# UI.net
KiCad netlist of a schematic drawn in Altium Designer
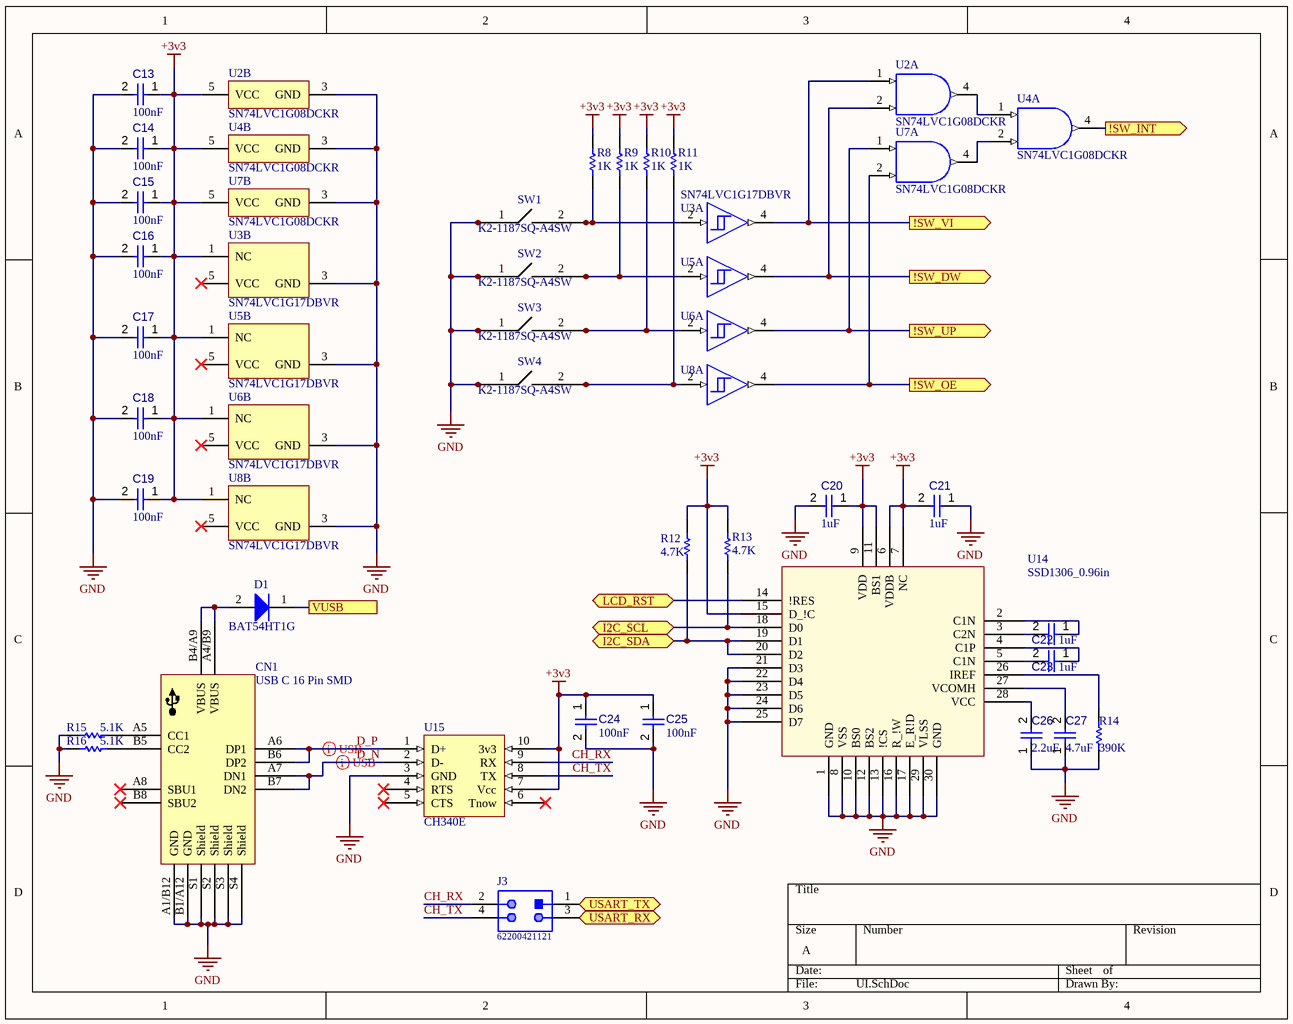
[diagram p0: UI.SchDoc]

(export (version "E")
  (design (tool "Eeschema 10.0.6"))
  (components
    (comp (ref "C13")
      (value "100nF")
      (footprint "CAPC2013X95X50ML10T25")
      (description "Chip Capacitor, 100 nF, +/- 10%, 50 V, 0805 (2012 Metric)")
      (fields (field (name "TOLERANCE") "10%") (field (name "Comment") "Capacitor 100 nF +/-10% 50 V 0805"))
      (libsource (lib "Aditya Sehgal") (part "CAP-NP-2"))
    )
    (comp (ref "C14")
      (value "100nF")
      (footprint "CAPC2013X95X50ML10T25")
      (description "Chip Capacitor, 100 nF, +/- 10%, 50 V, 0805 (2012 Metric)")
      (fields (field (name "TOLERANCE") "10%") (field (name "Comment") "Capacitor 100 nF +/-10% 50 V 0805"))
      (libsource (lib "Aditya Sehgal") (part "CAP-NP-2"))
    )
    (comp (ref "C15")
      (value "100nF")
      (footprint "CAPC2013X95X50ML10T25")
      (description "Chip Capacitor, 100 nF, +/- 10%, 50 V, 0805 (2012 Metric)")
      (fields (field (name "TOLERANCE") "10%") (field (name "Comment") "Capacitor 100 nF +/-10% 50 V 0805"))
      (libsource (lib "Aditya Sehgal") (part "CAP-NP-2"))
    )
    (comp (ref "C16")
      (value "100nF")
      (footprint "CAPC2013X95X50ML10T25")
      (description "Chip Capacitor, 100 nF, +/- 10%, 50 V, 0805 (2012 Metric)")
      (fields (field (name "TOLERANCE") "10%") (field (name "Comment") "Capacitor 100 nF +/-10% 50 V 0805"))
      (libsource (lib "Aditya Sehgal") (part "CAP-NP-2"))
    )
    (comp (ref "C17")
      (value "100nF")
      (footprint "CAPC2013X95X50ML10T25")
      (description "Chip Capacitor, 100 nF, +/- 10%, 50 V, 0805 (2012 Metric)")
      (fields (field (name "TOLERANCE") "10%") (field (name "Comment") "Capacitor 100 nF +/-10% 50 V 0805"))
      (libsource (lib "Aditya Sehgal") (part "CAP-NP-2"))
    )
    (comp (ref "C18")
      (value "100nF")
      (footprint "CAPC2013X95X50ML10T25")
      (description "Chip Capacitor, 100 nF, +/- 10%, 50 V, 0805 (2012 Metric)")
      (fields (field (name "TOLERANCE") "10%") (field (name "Comment") "Capacitor 100 nF +/-10% 50 V 0805"))
      (libsource (lib "Aditya Sehgal") (part "CAP-NP-2"))
    )
    (comp (ref "C19")
      (value "100nF")
      (footprint "CAPC2013X95X50ML10T25")
      (description "Chip Capacitor, 100 nF, +/- 10%, 50 V, 0805 (2012 Metric)")
      (fields (field (name "TOLERANCE") "10%") (field (name "Comment") "Capacitor 100 nF +/-10% 50 V 0805"))
      (libsource (lib "Aditya Sehgal") (part "CAP-NP-2"))
    )
    (comp (ref "C20")
      (value "1uF")
      (footprint "CAPC2013X95X50ML10T25")
      (description "Chip Capacitor, 100 nF, +/- 10%, 50 V, 0805 (2012 Metric)")
      (fields (field (name "TOLERANCE") "10%") (field (name "Comment") "Capacitor 100 nF +/-10% 50 V 0805"))
      (libsource (lib "Aditya Sehgal") (part "CAP-NP-2"))
    )
    (comp (ref "C21")
      (value "1uF")
      (footprint "CAPC2013X95X50ML10T25")
      (description "Chip Capacitor, 100 nF, +/- 10%, 50 V, 0805 (2012 Metric)")
      (fields (field (name "TOLERANCE") "10%") (field (name "Comment") "Capacitor 100 nF +/-10% 50 V 0805"))
      (libsource (lib "Aditya Sehgal") (part "CAP-NP-2"))
    )
    (comp (ref "C22")
      (value "1uF")
      (footprint "CAPC2013X95X50ML10T25")
      (description "Chip Capacitor, 100 nF, +/- 10%, 50 V, 0805 (2012 Metric)")
      (fields (field (name "TOLERANCE") "10%") (field (name "Comment") "Capacitor 100 nF +/-10% 50 V 0805"))
      (libsource (lib "Aditya Sehgal") (part "CAP-NP-2"))
    )
    (comp (ref "C23")
      (value "1uF")
      (footprint "CAPC2013X95X50ML10T25")
      (description "Chip Capacitor, 100 nF, +/- 10%, 50 V, 0805 (2012 Metric)")
      (fields (field (name "TOLERANCE") "10%") (field (name "Comment") "Capacitor 100 nF +/-10% 50 V 0805"))
      (libsource (lib "Aditya Sehgal") (part "CAP-NP-2"))
    )
    (comp (ref "C24")
      (value "100nF")
      (footprint "CAPC2013X95X50ML10T25")
      (description "Chip Capacitor, 100 nF, +/- 10%, 50 V, 0805 (2012 Metric)")
      (fields (field (name "TOLERANCE") "10%") (field (name "Comment") "Capacitor 100 nF +/-10% 50 V 0805"))
      (libsource (lib "Aditya Sehgal") (part "CAP-NP-2"))
    )
    (comp (ref "C25")
      (value "100nF")
      (footprint "CAPC2013X95X50ML10T25")
      (description "Chip Capacitor, 100 nF, +/- 10%, 50 V, 0805 (2012 Metric)")
      (fields (field (name "TOLERANCE") "10%") (field (name "Comment") "Capacitor 100 nF +/-10% 50 V 0805"))
      (libsource (lib "Aditya Sehgal") (part "CAP-NP-2"))
    )
    (comp (ref "C26")
      (value "2.2uF")
      (footprint "CAPC2013X95X50ML10T25")
      (description "Chip Capacitor, 100 nF, +/- 10%, 50 V, 0805 (2012 Metric)")
      (fields (field (name "TOLERANCE") "10%") (field (name "Comment") "Capacitor 100 nF +/-10% 50 V 0805"))
      (libsource (lib "Aditya Sehgal") (part "CAP-NP-2"))
    )
    (comp (ref "C27")
      (value "4.7uF")
      (footprint "CAPC2013X95X50ML10T25")
      (description "Chip Capacitor, 100 nF, +/- 10%, 50 V, 0805 (2012 Metric)")
      (fields (field (name "TOLERANCE") "10%") (field (name "Comment") "Capacitor 100 nF +/-10% 50 V 0805"))
      (libsource (lib "Aditya Sehgal") (part "CAP-NP-2"))
    )
    (comp (ref "CN1")
      (value "USB C 16 Pin SMD")
      (footprint "USB C 16 Pin SMD-Footprint-1")
      (description "C167321 Jing Extension")
      (libsource (lib "Aditya Sehgal") (part "USB C 16 Pin SMD"))
    )
    (comp (ref "D1")
      (value "BAT54HT1G")
      (footprint "ONSC-SOD-323-2-477-02_V")
      (description "Schottky Barrier Diode, 2-Pin SOD-323, Pb-Free, Tape and Reel")
      (fields (field (name "MANUFACTURER") "On Semiconductor"))
      (libsource (lib "Altium Content Vault") (part "ONSC-D-K1A2-2"))
    )
    (comp (ref "J3")
      (value "62200421121")
      (footprint "62200421121")
      (description "THT Vertical Pin Header WR-PHD, Pitch 1.27 mm, Dual Row, 4 pins")
      (fields (field (name "MANUFACTURER") "Wurth Elektronik") (field (name "PUBLISHER") "WurthElektronik"))
      (libsource (lib "Altium Content Vault") (part "WE-CN-2P-M-R4"))
    )
    (comp (ref "R8")
      (value "1K")
      (footprint "RESC2013X50X35ML15T15")
      (description "Chip Resistor, 0 Ohm, +/- 1%, 125 mW, -55 to 155 degC, 0805 (2012 Metric)")
      (fields (field (name "TOLERANCE") "1%") (field (name "POWER") "125mW"))
      (libsource (lib "Aditya Sehgal") (part "RES-2"))
    )
    (comp (ref "R9")
      (value "1K")
      (footprint "RESC2013X50X35ML15T15")
      (description "Chip Resistor, 0 Ohm, +/- 1%, 125 mW, -55 to 155 degC, 0805 (2012 Metric)")
      (fields (field (name "TOLERANCE") "1%") (field (name "POWER") "125mW"))
      (libsource (lib "Aditya Sehgal") (part "RES-2"))
    )
    (comp (ref "R10")
      (value "1K")
      (footprint "RESC2013X50X35ML15T15")
      (description "Chip Resistor, 0 Ohm, +/- 1%, 125 mW, -55 to 155 degC, 0805 (2012 Metric)")
      (fields (field (name "TOLERANCE") "1%") (field (name "POWER") "125mW"))
      (libsource (lib "Aditya Sehgal") (part "RES-2"))
    )
    (comp (ref "R11")
      (value "1K")
      (footprint "RESC2013X50X35ML15T15")
      (description "Chip Resistor, 0 Ohm, +/- 1%, 125 mW, -55 to 155 degC, 0805 (2012 Metric)")
      (fields (field (name "TOLERANCE") "1%") (field (name "POWER") "125mW"))
      (libsource (lib "Aditya Sehgal") (part "RES-2"))
    )
    (comp (ref "R12")
      (value "4.7K")
      (footprint "RESC2013X50X35ML15T15")
      (description "Chip Resistor, 0 Ohm, +/- 1%, 125 mW, -55 to 155 degC, 0805 (2012 Metric)")
      (fields (field (name "TOLERANCE") "1%") (field (name "POWER") "125mW"))
      (libsource (lib "Aditya Sehgal") (part "RES-2"))
    )
    (comp (ref "R13")
      (value "4.7K")
      (footprint "RESC2013X50X35ML15T15")
      (description "Chip Resistor, 0 Ohm, +/- 1%, 125 mW, -55 to 155 degC, 0805 (2012 Metric)")
      (fields (field (name "TOLERANCE") "1%") (field (name "POWER") "125mW"))
      (libsource (lib "Aditya Sehgal") (part "RES-2"))
    )
    (comp (ref "R14")
      (value "390K")
      (footprint "RESC2013X50X35ML15T15")
      (description "Chip Resistor, 0 Ohm, +/- 1%, 125 mW, -55 to 155 degC, 0805 (2012 Metric)")
      (fields (field (name "TOLERANCE") "1%") (field (name "POWER") "125mW"))
      (libsource (lib "Aditya Sehgal") (part "RES-2"))
    )
    (comp (ref "R15")
      (value "5.1K")
      (footprint "RESC2013X50X35ML15T15")
      (description "Chip Resistor, 0 Ohm, +/- 1%, 125 mW, -55 to 155 degC, 0805 (2012 Metric)")
      (fields (field (name "TOLERANCE") "1%") (field (name "POWER") "125mW"))
      (libsource (lib "Aditya Sehgal") (part "RES-2"))
    )
    (comp (ref "R16")
      (value "5.1K")
      (footprint "RESC2013X50X35ML15T15")
      (description "Chip Resistor, 0 Ohm, +/- 1%, 125 mW, -55 to 155 degC, 0805 (2012 Metric)")
      (fields (field (name "TOLERANCE") "1%") (field (name "POWER") "125mW"))
      (libsource (lib "Aditya Sehgal") (part "RES-2"))
    )
    (comp (ref "SW1")
      (value "K2-1187SQ-A4SW")
      (footprint "K2-1187SQ-A4SW-Footprint-1")
      (description "4 pin SMD switch")
      (libsource (lib "Aditya Sehgal") (part "K2-1187SQ-A4SW"))
    )
    (comp (ref "SW2")
      (value "K2-1187SQ-A4SW")
      (footprint "K2-1187SQ-A4SW-Footprint-1")
      (description "4 pin SMD switch")
      (libsource (lib "Aditya Sehgal") (part "K2-1187SQ-A4SW"))
    )
    (comp (ref "SW3")
      (value "K2-1187SQ-A4SW")
      (footprint "K2-1187SQ-A4SW-Footprint-1")
      (description "4 pin SMD switch")
      (libsource (lib "Aditya Sehgal") (part "K2-1187SQ-A4SW"))
    )
    (comp (ref "SW4")
      (value "K2-1187SQ-A4SW")
      (footprint "K2-1187SQ-A4SW-Footprint-1")
      (description "4 pin SMD switch")
      (libsource (lib "Aditya Sehgal") (part "K2-1187SQ-A4SW"))
    )
    (comp (ref "U2")
      (value "SN74LVC1G08DCKR")
      (footprint "DCK0005A_M")
      (description "Single 2-Input Positive-AND Gate, DCK0005A, LARGE T&R")
      (fields
        (field (name "GENERIC PART NUMBER") "SN74LVC1G08")
        (field (name "MANUFACTURER") "Texas Instruments")
      )
      (libsource (lib "Altium Content Vault") (part "TI-SN74XXX1X08-5"))
    )
    (comp (ref "U3")
      (value "SN74LVC1G17DBVR")
      (footprint "DBV0005A_L")
      (description "Single Schmitt-Trigger Buffer, DBV0005A, LARGE T&R")
      (fields
        (field (name "MANUFACTURER") "Texas Instruments")
        (field (name "GENERIC PART NUMBER") "SN74LVC1G17")
      )
      (libsource (lib "Altium Content Vault") (part "TI-SN74XXX1XXX-XX-5-SCHMITT"))
    )
    (comp (ref "U4")
      (value "SN74LVC1G08DCKR")
      (footprint "DCK0005A_M")
      (description "Single 2-Input Positive-AND Gate, DCK0005A, LARGE T&R")
      (fields
        (field (name "GENERIC PART NUMBER") "SN74LVC1G08")
        (field (name "MANUFACTURER") "Texas Instruments")
      )
      (libsource (lib "Altium Content Vault") (part "TI-SN74XXX1X08-5"))
    )
    (comp (ref "U5")
      (value "SN74LVC1G17DBVR")
      (footprint "DBV0005A_L")
      (description "Single Schmitt-Trigger Buffer, DBV0005A, LARGE T&R")
      (fields
        (field (name "MANUFACTURER") "Texas Instruments")
        (field (name "GENERIC PART NUMBER") "SN74LVC1G17")
      )
      (libsource (lib "Altium Content Vault") (part "TI-SN74XXX1XXX-XX-5-SCHMITT"))
    )
    (comp (ref "U6")
      (value "SN74LVC1G17DBVR")
      (footprint "DBV0005A_L")
      (description "Single Schmitt-Trigger Buffer, DBV0005A, LARGE T&R")
      (fields
        (field (name "MANUFACTURER") "Texas Instruments")
        (field (name "GENERIC PART NUMBER") "SN74LVC1G17")
      )
      (libsource (lib "Altium Content Vault") (part "TI-SN74XXX1XXX-XX-5-SCHMITT"))
    )
    (comp (ref "U7")
      (value "SN74LVC1G08DCKR")
      (footprint "DCK0005A_M")
      (description "Single 2-Input Positive-AND Gate, DCK0005A, LARGE T&R")
      (fields
        (field (name "GENERIC PART NUMBER") "SN74LVC1G08")
        (field (name "MANUFACTURER") "Texas Instruments")
      )
      (libsource (lib "Altium Content Vault") (part "TI-SN74XXX1X08-5"))
    )
    (comp (ref "U8")
      (value "SN74LVC1G17DBVR")
      (footprint "DBV0005A_L")
      (description "Single Schmitt-Trigger Buffer, DBV0005A, LARGE T&R")
      (fields
        (field (name "MANUFACTURER") "Texas Instruments")
        (field (name "GENERIC PART NUMBER") "SN74LVC1G17")
      )
      (libsource (lib "Altium Content Vault") (part "TI-SN74XXX1XXX-XX-5-SCHMITT"))
    )
    (comp (ref "U14")
      (value "SSD1306_0.96in")
      (footprint "SSD1306_0.96in-Footprint-1")
      (description "C91755")
      (libsource (lib "Aditya Sehgal") (part "SSD1306_0.96in"))
    )
    (comp (ref "U15")
      (value "CH340E")
      (footprint "TSSOP50P490X110-10N")
      (description "USB to UART Converter")
      (libsource (lib "Aditya Sehgal") (part "CH340E"))
    )
  )
  (nets
    (net (code "1") (name "+3v3") (class "Default")
      (node (ref "C13") (pin "1") (pinfunction "1_1") (pintype "passive"))
      (node (ref "C14") (pin "1") (pinfunction "1_1") (pintype "passive"))
      (node (ref "C15") (pin "1") (pinfunction "1_1") (pintype "passive"))
      (node (ref "C16") (pin "1") (pinfunction "1_1") (pintype "passive"))
      (node (ref "C17") (pin "1") (pinfunction "1_1") (pintype "passive"))
      (node (ref "C18") (pin "1") (pinfunction "1_1") (pintype "passive"))
      (node (ref "C19") (pin "1") (pinfunction "1_1") (pintype "passive"))
      (node (ref "C20") (pin "1") (pinfunction "1_1") (pintype "passive"))
      (node (ref "C21") (pin "2") (pinfunction "2_2") (pintype "passive"))
      (node (ref "C24") (pin "1") (pinfunction "1_1") (pintype "passive"))
      (node (ref "C25") (pin "1") (pinfunction "1_1") (pintype "passive"))
      (node (ref "R10") (pin "2") (pinfunction "2_2") (pintype "passive"))
      (node (ref "R11") (pin "2") (pinfunction "2_2") (pintype "passive"))
      (node (ref "R12") (pin "2") (pinfunction "2_2") (pintype "passive"))
      (node (ref "R13") (pin "2") (pinfunction "2_2") (pintype "passive"))
      (node (ref "R8") (pin "2") (pinfunction "2_2") (pintype "passive"))
      (node (ref "R9") (pin "2") (pinfunction "2_2") (pintype "passive"))
      (node (ref "U14") (pin "11") (pinfunction "BS1_11") (pintype "passive"))
      (node (ref "U14") (pin "15") (pinfunction "D_!C_15") (pintype "passive"))
      (node (ref "U14") (pin "6") (pinfunction "VDDB_6") (pintype "passive"))
      (node (ref "U14") (pin "7") (pinfunction "NC_7") (pintype "passive"))
      (node (ref "U14") (pin "9") (pinfunction "VDD_9") (pintype "passive"))
      (node (ref "U15") (pin "10") (pinfunction "3v3_10") (pintype "input"))
      (node (ref "U15") (pin "7") (pinfunction "Vcc_7") (pintype "input"))
      (node (ref "U2") (pin "5") (pinfunction "VCC_5") (pintype "power_in"))
      (node (ref "U3") (pin "1") (pinfunction "NC_1") (pintype "passive"))
      (node (ref "U4") (pin "5") (pinfunction "VCC_5") (pintype "power_in"))
      (node (ref "U5") (pin "1") (pinfunction "NC_1") (pintype "passive"))
      (node (ref "U6") (pin "1") (pinfunction "NC_1") (pintype "passive"))
      (node (ref "U7") (pin "5") (pinfunction "VCC_5") (pintype "power_in"))
      (node (ref "U8") (pin "1") (pinfunction "NC_1") (pintype "passive"))
    )
    (net (code "2") (name "/!SW_DW") (class "Default")
      (node (ref "U2") (pin "2") (pinfunction "B_2") (pintype "input"))
      (node (ref "U5") (pin "4") (pinfunction "Y_4") (pintype "output"))
    )
    (net (code "3") (name "/!SW_INT") (class "Default")
      (node (ref "U4") (pin "4") (pinfunction "Y_4") (pintype "output"))
    )
    (net (code "4") (name "/!SW_OE") (class "Default")
      (node (ref "U7") (pin "2") (pinfunction "B_2") (pintype "input"))
      (node (ref "U8") (pin "4") (pinfunction "Y_4") (pintype "output"))
    )
    (net (code "5") (name "/!SW_UP") (class "Default")
      (node (ref "U6") (pin "4") (pinfunction "Y_4") (pintype "output"))
      (node (ref "U7") (pin "1") (pinfunction "A_1") (pintype "input"))
    )
    (net (code "6") (name "/!SW_VI") (class "Default")
      (node (ref "U2") (pin "1") (pinfunction "A_1") (pintype "input"))
      (node (ref "U3") (pin "4") (pinfunction "Y_4") (pintype "output"))
    )
    (net (code "7") (name "/CH_RX") (class "Default")
      (node (ref "J3") (pin "2") (pinfunction "2_2") (pintype "passive"))
      (node (ref "U15") (pin "9") (pinfunction "RX_9") (pintype "input"))
    )
    (net (code "8") (name "/CH_TX") (class "Default")
      (node (ref "J3") (pin "4") (pinfunction "4_4") (pintype "passive"))
      (node (ref "U15") (pin "8") (pinfunction "TX_8") (pintype "input"))
    )
    (net (code "9") (name "/D_N") (class "Default")
      (node (ref "CN1") (pin "A7") (pinfunction "DN1_A7") (pintype "passive"))
      (node (ref "CN1") (pin "B7") (pinfunction "DN2_B7") (pintype "passive"))
      (node (ref "U15") (pin "2") (pinfunction "D-_2") (pintype "input"))
    )
    (net (code "10") (name "/D_P") (class "Default")
      (node (ref "CN1") (pin "A6") (pinfunction "DP1_A6") (pintype "passive"))
      (node (ref "CN1") (pin "B6") (pinfunction "DP2_B6") (pintype "passive"))
      (node (ref "U15") (pin "1") (pinfunction "D+_1") (pintype "input"))
    )
    (net (code "11") (name "/I2C_SCL") (class "Default")
      (node (ref "R13") (pin "1") (pinfunction "1_1") (pintype "passive"))
      (node (ref "U14") (pin "18") (pinfunction "D0_18") (pintype "passive"))
    )
    (net (code "12") (name "/I2C_SDA") (class "Default")
      (node (ref "R12") (pin "1") (pinfunction "1_1") (pintype "passive"))
      (node (ref "U14") (pin "19") (pinfunction "D1_19") (pintype "passive"))
      (node (ref "U14") (pin "20") (pinfunction "D2_20") (pintype "passive"))
    )
    (net (code "13") (name "/LCD_RST") (class "Default")
      (node (ref "U14") (pin "14") (pinfunction "!RES_14") (pintype "passive"))
    )
    (net (code "14") (name "/USART_RX") (class "Default")
      (node (ref "J3") (pin "3") (pinfunction "3_3") (pintype "passive"))
    )
    (net (code "15") (name "/USART_TX") (class "Default")
      (node (ref "J3") (pin "1") (pinfunction "1_1") (pintype "passive"))
    )
    (net (code "16") (name "/VUSB") (class "Default")
      (node (ref "D1") (pin "1") (pinfunction "K_1") (pintype "passive"))
    )
    (net (code "17") (name "GND") (class "Default")
      (node (ref "C13") (pin "2") (pinfunction "2_2") (pintype "passive"))
      (node (ref "C14") (pin "2") (pinfunction "2_2") (pintype "passive"))
      (node (ref "C15") (pin "2") (pinfunction "2_2") (pintype "passive"))
      (node (ref "C16") (pin "2") (pinfunction "2_2") (pintype "passive"))
      (node (ref "C17") (pin "2") (pinfunction "2_2") (pintype "passive"))
      (node (ref "C18") (pin "2") (pinfunction "2_2") (pintype "passive"))
      (node (ref "C19") (pin "2") (pinfunction "2_2") (pintype "passive"))
      (node (ref "C20") (pin "2") (pinfunction "2_2") (pintype "passive"))
      (node (ref "C21") (pin "1") (pinfunction "1_1") (pintype "passive"))
      (node (ref "C24") (pin "2") (pinfunction "2_2") (pintype "passive"))
      (node (ref "C25") (pin "2") (pinfunction "2_2") (pintype "passive"))
      (node (ref "C26") (pin "1") (pinfunction "1_1") (pintype "passive"))
      (node (ref "C27") (pin "1") (pinfunction "1_1") (pintype "passive"))
      (node (ref "CN1") (pin "A1/B12") (pinfunction "GND_A1/B12") (pintype "power_in"))
      (node (ref "CN1") (pin "B1/A12") (pinfunction "GND_B1/A12") (pintype "power_in"))
      (node (ref "CN1") (pin "S1") (pinfunction "Shield_S1") (pintype "power_in"))
      (node (ref "CN1") (pin "S2") (pinfunction "Shield_S2") (pintype "power_in"))
      (node (ref "CN1") (pin "S3") (pinfunction "Shield_S3") (pintype "power_in"))
      (node (ref "CN1") (pin "S4") (pinfunction "Shield_S4") (pintype "power_in"))
      (node (ref "R14") (pin "2") (pinfunction "2_2") (pintype "passive"))
      (node (ref "R15") (pin "2") (pinfunction "2_2") (pintype "passive"))
      (node (ref "R16") (pin "2") (pinfunction "2_2") (pintype "passive"))
      (node (ref "SW1") (pin "1") (pinfunction "1_1") (pintype "passive"))
      (node (ref "SW1") (pin "3") (pinfunction "3_3") (pintype "passive"))
      (node (ref "SW2") (pin "1") (pinfunction "1_1") (pintype "passive"))
      (node (ref "SW2") (pin "3") (pinfunction "3_3") (pintype "passive"))
      (node (ref "SW3") (pin "1") (pinfunction "1_1") (pintype "passive"))
      (node (ref "SW3") (pin "3") (pinfunction "3_3") (pintype "passive"))
      (node (ref "SW4") (pin "1") (pinfunction "1_1") (pintype "passive"))
      (node (ref "SW4") (pin "3") (pinfunction "3_3") (pintype "passive"))
      (node (ref "U14") (pin "1") (pinfunction "GND_1") (pintype "passive"))
      (node (ref "U14") (pin "10") (pinfunction "BS0_10") (pintype "passive"))
      (node (ref "U14") (pin "12") (pinfunction "BS2_12") (pintype "passive"))
      (node (ref "U14") (pin "13") (pinfunction "!CS_13") (pintype "passive"))
      (node (ref "U14") (pin "16") (pinfunction "R_!W_16") (pintype "passive"))
      (node (ref "U14") (pin "17") (pinfunction "E_R!D_17") (pintype "passive"))
      (node (ref "U14") (pin "21") (pinfunction "D3_21") (pintype "passive"))
      (node (ref "U14") (pin "22") (pinfunction "D4_22") (pintype "passive"))
      (node (ref "U14") (pin "23") (pinfunction "D5_23") (pintype "passive"))
      (node (ref "U14") (pin "24") (pinfunction "D6_24") (pintype "passive"))
      (node (ref "U14") (pin "25") (pinfunction "D7_25") (pintype "passive"))
      (node (ref "U14") (pin "29") (pinfunction "VLSS_29") (pintype "passive"))
      (node (ref "U14") (pin "30") (pinfunction "GND_30") (pintype "passive"))
      (node (ref "U14") (pin "8") (pinfunction "VSS_8") (pintype "passive"))
      (node (ref "U15") (pin "3") (pinfunction "GND_3") (pintype "input"))
      (node (ref "U2") (pin "3") (pinfunction "GND_3") (pintype "power_in"))
      (node (ref "U3") (pin "3") (pinfunction "GND_3") (pintype "power_in"))
      (node (ref "U4") (pin "3") (pinfunction "GND_3") (pintype "power_in"))
      (node (ref "U5") (pin "3") (pinfunction "GND_3") (pintype "power_in"))
      (node (ref "U6") (pin "3") (pinfunction "GND_3") (pintype "power_in"))
      (node (ref "U7") (pin "3") (pinfunction "GND_3") (pintype "power_in"))
      (node (ref "U8") (pin "3") (pinfunction "GND_3") (pintype "power_in"))
    )
    (net (code "18") (name "Net-(C22-Pad1)") (class "Default")
      (node (ref "C22") (pin "1") (pinfunction "1_1") (pintype "passive"))
      (node (ref "U14") (pin "2") (pinfunction "C1N_2") (pintype "passive"))
    )
    (net (code "19") (name "Net-(C23-Pad2)") (class "Default")
      (node (ref "C23") (pin "2") (pinfunction "2_2") (pintype "passive"))
      (node (ref "U14") (pin "5") (pinfunction "C1N_5") (pintype "passive"))
    )
    (net (code "20") (name "Net-(CN1-CC1)") (class "Default")
      (node (ref "CN1") (pin "A5") (pinfunction "CC1_A5") (pintype "passive"))
      (node (ref "R15") (pin "1") (pinfunction "1_1") (pintype "passive"))
    )
    (net (code "21") (name "Net-(CN1-CC2)") (class "Default")
      (node (ref "CN1") (pin "B5") (pinfunction "CC2_B5") (pintype "passive"))
      (node (ref "R16") (pin "1") (pinfunction "1_1") (pintype "passive"))
    )
    (net (code "22") (name "Net-(D1-A)") (class "Default")
      (node (ref "CN1") (pin "A4/B9") (pinfunction "VBUS_A4/B9") (pintype "power_in"))
      (node (ref "CN1") (pin "B4/A9") (pinfunction "VBUS_B4/A9") (pintype "power_in"))
      (node (ref "D1") (pin "2") (pinfunction "A_2") (pintype "passive"))
    )
    (net (code "23") (name "Net-(U2A-Y)") (class "Default")
      (node (ref "U2") (pin "4") (pinfunction "Y_4") (pintype "output"))
      (node (ref "U4") (pin "1") (pinfunction "A_1") (pintype "input"))
    )
    (net (code "24") (name "Net-(U3A-A)") (class "Default")
      (node (ref "R8") (pin "1") (pinfunction "1_1") (pintype "passive"))
      (node (ref "SW1") (pin "2") (pinfunction "2_2") (pintype "passive"))
      (node (ref "SW1") (pin "4") (pinfunction "4_4") (pintype "passive"))
      (node (ref "U3") (pin "2") (pinfunction "A_2") (pintype "input"))
    )
    (net (code "25") (name "Net-(U4A-B)") (class "Default")
      (node (ref "U4") (pin "2") (pinfunction "B_2") (pintype "input"))
      (node (ref "U7") (pin "4") (pinfunction "Y_4") (pintype "output"))
    )
    (net (code "26") (name "Net-(U5A-A)") (class "Default")
      (node (ref "R9") (pin "1") (pinfunction "1_1") (pintype "passive"))
      (node (ref "SW2") (pin "2") (pinfunction "2_2") (pintype "passive"))
      (node (ref "SW2") (pin "4") (pinfunction "4_4") (pintype "passive"))
      (node (ref "U5") (pin "2") (pinfunction "A_2") (pintype "input"))
    )
    (net (code "27") (name "Net-(U6A-A)") (class "Default")
      (node (ref "R10") (pin "1") (pinfunction "1_1") (pintype "passive"))
      (node (ref "SW3") (pin "2") (pinfunction "2_2") (pintype "passive"))
      (node (ref "SW3") (pin "4") (pinfunction "4_4") (pintype "passive"))
      (node (ref "U6") (pin "2") (pinfunction "A_2") (pintype "input"))
    )
    (net (code "28") (name "Net-(U8A-A)") (class "Default")
      (node (ref "R11") (pin "1") (pinfunction "1_1") (pintype "passive"))
      (node (ref "SW4") (pin "2") (pinfunction "2_2") (pintype "passive"))
      (node (ref "SW4") (pin "4") (pinfunction "4_4") (pintype "passive"))
      (node (ref "U8") (pin "2") (pinfunction "A_2") (pintype "input"))
    )
    (net (code "29") (name "Net-(U14-C1P)") (class "Default")
      (node (ref "C23") (pin "1") (pinfunction "1_1") (pintype "passive"))
      (node (ref "U14") (pin "4") (pinfunction "C1P_4") (pintype "passive"))
    )
    (net (code "30") (name "Net-(U14-C2N)") (class "Default")
      (node (ref "C22") (pin "2") (pinfunction "2_2") (pintype "passive"))
      (node (ref "U14") (pin "3") (pinfunction "C2N_3") (pintype "passive"))
    )
    (net (code "31") (name "Net-(U14-IREF)") (class "Default")
      (node (ref "R14") (pin "1") (pinfunction "1_1") (pintype "passive"))
      (node (ref "U14") (pin "26") (pinfunction "IREF_26") (pintype "passive"))
    )
    (net (code "32") (name "Net-(U14-VCC)") (class "Default")
      (node (ref "C26") (pin "2") (pinfunction "2_2") (pintype "passive"))
      (node (ref "U14") (pin "28") (pinfunction "VCC_28") (pintype "passive"))
    )
    (net (code "33") (name "Net-(U14-VCOMH)") (class "Default")
      (node (ref "C27") (pin "2") (pinfunction "2_2") (pintype "passive"))
      (node (ref "U14") (pin "27") (pinfunction "VCOMH_27") (pintype "passive"))
    )
    (net (code "34") (name "unconnected-(CN1-S5-PadH2)") (class "Default")
      (node (ref "CN1") (pin "H2") (pinfunction "S5_H2") (pintype "passive"))
    )
    (net (code "35") (name "unconnected-(CN1-S6-PadH1)") (class "Default")
      (node (ref "CN1") (pin "H1") (pinfunction "S6_H1") (pintype "passive"))
    )
    (net (code "36") (name "unconnected-(CN1-SBU1-PadA8)") (class "Default")
      (node (ref "CN1") (pin "A8") (pinfunction "SBU1_A8") (pintype "passive+no_connect"))
    )
    (net (code "37") (name "unconnected-(CN1-SBU2-PadB8)") (class "Default")
      (node (ref "CN1") (pin "B8") (pinfunction "SBU2_B8") (pintype "passive+no_connect"))
    )
    (net (code "38") (name "unconnected-(U3B-VCC-Pad5)") (class "Default")
      (node (ref "U3") (pin "5") (pinfunction "VCC_5") (pintype "power_in+no_connect"))
    )
    (net (code "39") (name "unconnected-(U5B-VCC-Pad5)") (class "Default")
      (node (ref "U5") (pin "5") (pinfunction "VCC_5") (pintype "power_in+no_connect"))
    )
    (net (code "40") (name "unconnected-(U6B-VCC-Pad5)") (class "Default")
      (node (ref "U6") (pin "5") (pinfunction "VCC_5") (pintype "power_in+no_connect"))
    )
    (net (code "41") (name "unconnected-(U8B-VCC-Pad5)") (class "Default")
      (node (ref "U8") (pin "5") (pinfunction "VCC_5") (pintype "power_in+no_connect"))
    )
    (net (code "42") (name "unconnected-(U14-mech-Pad31)") (class "Default")
      (node (ref "U14") (pin "31") (pinfunction "mech_31") (pintype "passive"))
    )
    (net (code "43") (name "unconnected-(U15-CTS-Pad5)") (class "Default")
      (node (ref "U15") (pin "5") (pinfunction "CTS_5") (pintype "input+no_connect"))
    )
    (net (code "44") (name "unconnected-(U15-RTS-Pad4)") (class "Default")
      (node (ref "U15") (pin "4") (pinfunction "RTS_4") (pintype "input+no_connect"))
    )
    (net (code "45") (name "unconnected-(U15-Tnow-Pad6)") (class "Default")
      (node (ref "U15") (pin "6") (pinfunction "Tnow_6") (pintype "input+no_connect"))
    )
  )
)
